# ST_LINK-Wiki.net
KiCad netlist of a schematic drawn in Altium Designer
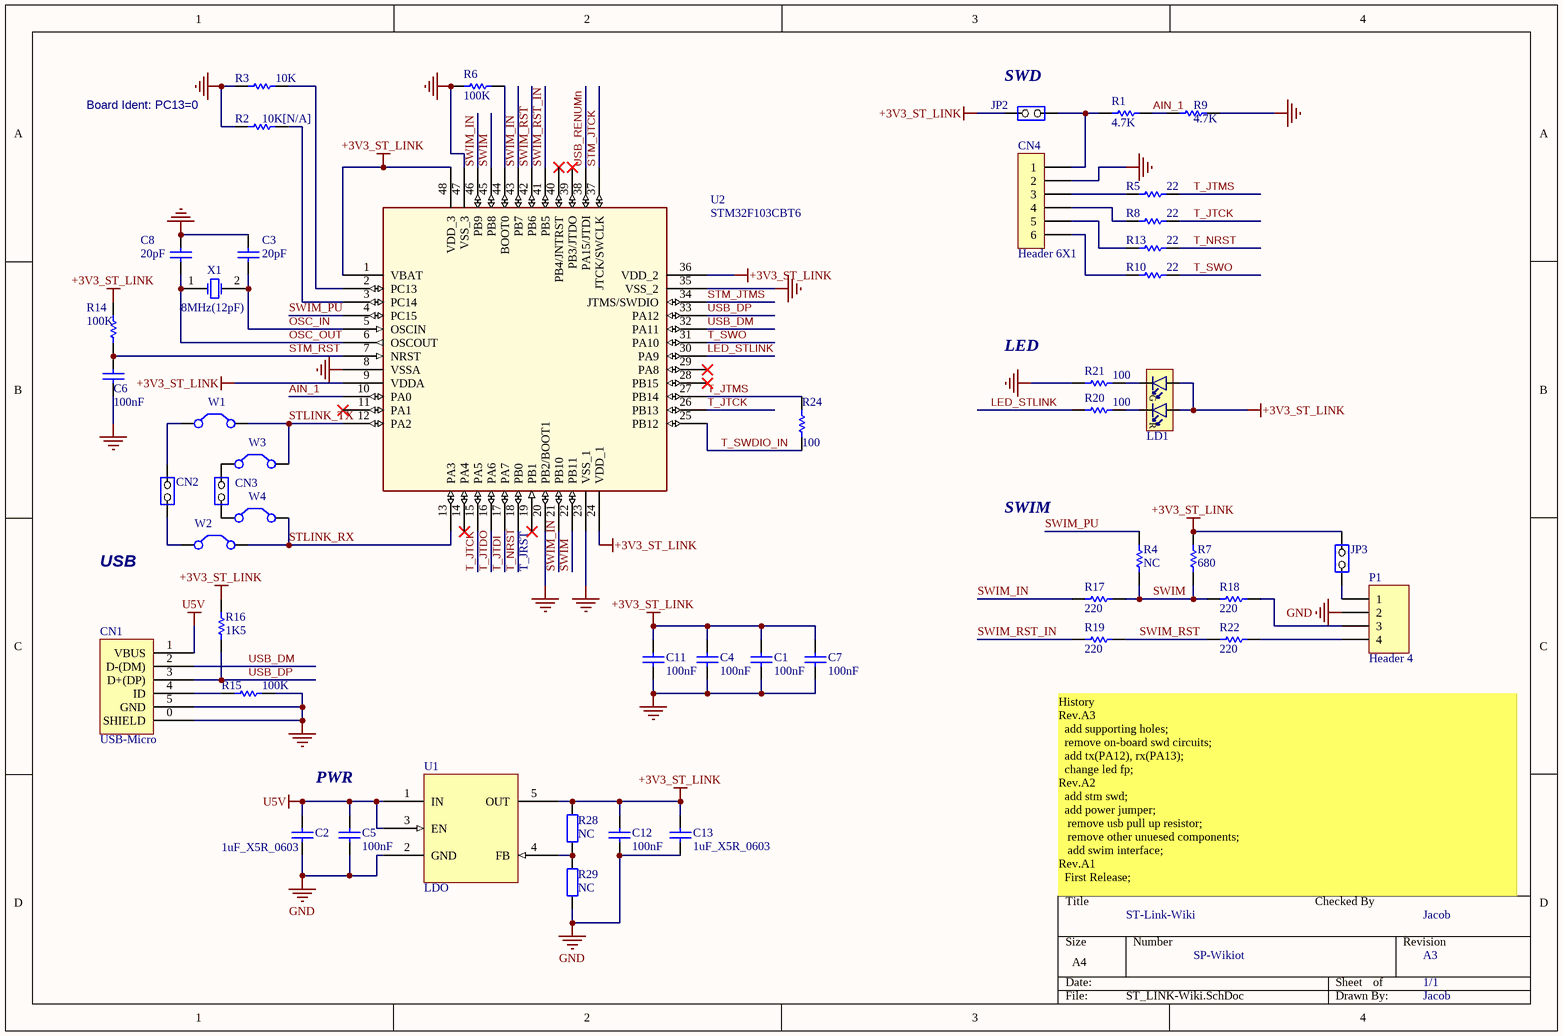
[diagram p0: ST_LINK-Wiki.SchDoc]

(export (version "E")
  (design (tool "Eeschema 10.0.6"))
  (components
    (comp (ref "C1")
      (value "100nF")
      (footprint "0603C")
      (description "Capacitor 0402 / 0603 / 0805")
      (libsource (lib "MCD_TOOLS") (part "Capacitor_ST"))
    )
    (comp (ref "C2")
      (value "1uF_X5R_0603")
      (footprint "0603C")
      (description "0603  X5R 1礔")
      (fields (field (name "TOLERANCE") "10%"))
      (libsource (lib "MB963_1") (part "CAP SMD 0603  X5R 1礔 25V 10%"))
    )
    (comp (ref "C3")
      (value "20pF")
      (footprint "0603C")
      (description "Capacitor 0402 / 0603 / 0805")
      (libsource (lib "MCD_TOOLS") (part "Capacitor_ST"))
    )
    (comp (ref "C4")
      (value "100nF")
      (footprint "0603C")
      (description "Capacitor 0402 / 0603 / 0805")
      (libsource (lib "MCD_TOOLS") (part "Capacitor_ST"))
    )
    (comp (ref "C5")
      (value "100nF")
      (footprint "0603C")
      (description "Capacitor 0402 / 0603 / 0805")
      (libsource (lib "MCD_TOOLS") (part "Capacitor_ST"))
    )
    (comp (ref "C6")
      (value "100nF")
      (footprint "0603C")
      (description "Capacitor 0402 / 0603 / 0805")
      (libsource (lib "MCD_TOOLS") (part "Capacitor_ST"))
    )
    (comp (ref "C7")
      (value "100nF")
      (footprint "0603C")
      (description "Capacitor 0402 / 0603 / 0805")
      (libsource (lib "MCD_TOOLS") (part "Capacitor_ST"))
    )
    (comp (ref "C8")
      (value "20pF")
      (footprint "0603C")
      (description "Capacitor 0402 / 0603 / 0805")
      (libsource (lib "MCD_TOOLS") (part "Capacitor_ST"))
    )
    (comp (ref "C11")
      (value "100nF")
      (footprint "0603C")
      (description "Capacitor 0402 / 0603 / 0805")
      (libsource (lib "MCD_TOOLS") (part "Capacitor_ST"))
    )
    (comp (ref "C12")
      (value "100nF")
      (footprint "0603C")
      (description "Capacitor 0402 / 0603 / 0805")
      (libsource (lib "MCD_TOOLS") (part "Capacitor_ST"))
    )
    (comp (ref "C13")
      (value "1uF_X5R_0603")
      (footprint "0603C")
      (description "0603  X5R 1礔")
      (fields (field (name "TOLERANCE") "10%"))
      (libsource (lib "MB963_1") (part "CAP SMD 0603  X5R 1礔 25V 10%"))
    )
    (comp (ref "CN1")
      (value "USB-Micro")
      (footprint "USB-MICRO-Lite")
      (libsource (lib "Connector") (part "USB-Micro"))
    )
    (comp (ref "CN2") (value "~") (footprint "HDR1X2-L/2.54MM") (libsource (lib "MCD_TOOLS") (part "JP2")))
    (comp (ref "CN3") (value "~") (footprint "HDR1X2-L/2.54MM") (libsource (lib "MCD_TOOLS") (part "JP2")))
    (comp (ref "CN4")
      (value "Header 6X1")
      (footprint "HDR1X6-L/2.54MM")
      (description "Header, 6-Pin, Single row")
      (fields (field (name "PUBLISHER") "Altium Limited"))
      (libsource (lib "Nucleo_64") (part "Header 6X1"))
    )
    (comp (ref "JP2") (value "~") (footprint "HDR1X2/2.54mm") (libsource (lib "*") (part "JP2")))
    (comp (ref "JP3") (value "~") (footprint "HDR1X2/2.54mm") (libsource (lib "*") (part "JP2")))
    (comp (ref "LD1")
      (value "LTST-C195KGJRKT")
      (footprint "0805-LED-Bi")
      (description "Avago, HSMF-A203 Bi-Color LED")
      (fields
        (field (name "MANUFACTURER") "Lite-On Inc")
        (field (name "2ND SOURCE PART NUMBER") "859-LTST-C195KGJRKT")
        (field (name "PUBLISHER") "Nordic Semiconductor")
      )
      (libsource (lib "Misc") (part "LED-DUAL"))
    )
    (comp (ref "P1")
      (value "Header 4")
      (footprint "HDR1X4-L/2.54MM")
      (description "Header, 4-Pin")
      (fields (field (name "PUBLISHER") "Altium Limited"))
      (libsource (lib "Miscellaneous Connectors") (part "Header 4"))
    )
    (comp (ref "R1")
      (value "4.7K")
      (footprint "0603R")
      (description "Resistor 0402 / 0603 / 0805")
      (libsource (lib "Miscellaneous Devices") (part "Res1"))
    )
    (comp (ref "R2")
      (value "10K[N/A]")
      (footprint "0603R")
      (description "Resistor 0402 / 0603 / 0805")
      (libsource (lib "Miscellaneous Devices") (part "Res1"))
    )
    (comp (ref "R3")
      (value "10K")
      (footprint "0603R")
      (description "Resistor 0402 / 0603 / 0805")
      (libsource (lib "Miscellaneous Devices") (part "Res1"))
    )
    (comp (ref "R4")
      (value "NC")
      (footprint "0603R")
      (description "Resistor 0402 / 0603 / 0805")
      (libsource (lib "Miscellaneous Devices") (part "Res1"))
    )
    (comp (ref "R5")
      (value "22")
      (footprint "0603R")
      (description "Resistor 0402 / 0603 / 0805")
      (libsource (lib "Miscellaneous Devices") (part "Res1"))
    )
    (comp (ref "R6")
      (value "100K")
      (footprint "0603R")
      (description "Resistor 0402 / 0603 / 0805")
      (libsource (lib "Miscellaneous Devices") (part "Res1"))
    )
    (comp (ref "R7")
      (value "680")
      (footprint "0603R")
      (description "Resistor 0402 / 0603 / 0805")
      (libsource (lib "Miscellaneous Devices") (part "Res1"))
    )
    (comp (ref "R8")
      (value "22")
      (footprint "0603R")
      (description "Resistor 0402 / 0603 / 0805")
      (libsource (lib "Miscellaneous Devices") (part "Res1"))
    )
    (comp (ref "R9")
      (value "4.7K")
      (footprint "0603R")
      (description "Resistor 0402 / 0603 / 0805")
      (libsource (lib "Miscellaneous Devices") (part "Res1"))
    )
    (comp (ref "R10")
      (value "22")
      (footprint "0603R")
      (description "Resistor 0402 / 0603 / 0805")
      (libsource (lib "Miscellaneous Devices") (part "Res1"))
    )
    (comp (ref "R13")
      (value "22")
      (footprint "0603R")
      (description "Resistor 0402 / 0603 / 0805")
      (libsource (lib "Miscellaneous Devices") (part "Res1"))
    )
    (comp (ref "R14")
      (value "100K")
      (footprint "0603R")
      (description "Resistor 0402 / 0603 / 0805")
      (libsource (lib "Miscellaneous Devices") (part "Res1"))
    )
    (comp (ref "R15")
      (value "100K")
      (footprint "0603R")
      (description "Resistor 0402 / 0603 / 0805")
      (libsource (lib "Miscellaneous Devices") (part "Res1"))
    )
    (comp (ref "R16")
      (value "1K5")
      (footprint "0603R")
      (description "Resistor 0402 / 0603 / 0805")
      (libsource (lib "Miscellaneous Devices") (part "Res1"))
    )
    (comp (ref "R17")
      (value "220")
      (footprint "0603R")
      (description "Resistor 0402 / 0603 / 0805")
      (libsource (lib "Miscellaneous Devices") (part "Res1"))
    )
    (comp (ref "R18")
      (value "220")
      (footprint "0603R")
      (description "Resistor 0402 / 0603 / 0805")
      (libsource (lib "Miscellaneous Devices") (part "Res1"))
    )
    (comp (ref "R19")
      (value "220")
      (footprint "0603R")
      (description "Resistor 0402 / 0603 / 0805")
      (libsource (lib "Miscellaneous Devices") (part "Res1"))
    )
    (comp (ref "R20")
      (value "100")
      (footprint "0603R")
      (description "Resistor 0402 / 0603 / 0805")
      (libsource (lib "Miscellaneous Devices") (part "Res1"))
    )
    (comp (ref "R21")
      (value "100")
      (footprint "0603R")
      (description "Resistor 0402 / 0603 / 0805")
      (libsource (lib "Miscellaneous Devices") (part "Res1"))
    )
    (comp (ref "R22")
      (value "220")
      (footprint "0603R")
      (description "Resistor 0402 / 0603 / 0805")
      (libsource (lib "Miscellaneous Devices") (part "Res1"))
    )
    (comp (ref "R24")
      (value "100")
      (footprint "0603R")
      (description "Resistor 0402 / 0603 / 0805")
      (libsource (lib "Miscellaneous Devices") (part "Res1"))
    )
    (comp (ref "R28")
      (value "NC")
      (footprint "0603M")
      (description "Resistor")
      (fields (field (name "PUBLISHER") "Altium Limited"))
      (libsource (lib "") (part "Res2_1"))
    )
    (comp (ref "R29")
      (value "NC")
      (footprint "0603M")
      (description "Resistor")
      (fields (field (name "PUBLISHER") "Altium Limited"))
      (libsource (lib "Miscellaneous Devices") (part "Res2"))
    )
    (comp (ref "U1")
      (value "LDO")
      (footprint "SOT23-5")
      (description "General LDO SOT23-5")
      (libsource (lib "Power") (part "LDO-SOT23-5"))
    )
    (comp (ref "U2")
      (value "STM32F103CBT6")
      (footprint "QFP48 7X7")
      (description "Medium-density performance line ARM-based 32-bit MCU with 64KB Flash")
      (libsource (lib "Nucleo_64") (part "STM32F103CBT6"))
    )
    (comp (ref "W1")
      (value "Jumper2-1")
      (footprint "JP2_SMD")
      (description "Jumper Wire")
      (fields (field (name "PUBLISHER") "Altium Limited"))
      (libsource (lib "Misc") (part "Jumper2-1"))
    )
    (comp (ref "W2")
      (value "Jumper2-1")
      (footprint "JP2_SMD")
      (description "Jumper Wire")
      (fields (field (name "PUBLISHER") "Altium Limited"))
      (libsource (lib "Misc") (part "Jumper2-1"))
    )
    (comp (ref "W3")
      (value "Jumper2-1")
      (footprint "JP2_SMD")
      (description "Jumper Wire")
      (fields (field (name "PUBLISHER") "Altium Limited"))
      (libsource (lib "Misc") (part "Jumper2-1"))
    )
    (comp (ref "W4")
      (value "Jumper2-1")
      (footprint "JP2_SMD")
      (description "Jumper Wire")
      (fields (field (name "PUBLISHER") "Altium Limited"))
      (libsource (lib "Misc") (part "Jumper2-1"))
    )
    (comp (ref "X1")
      (value "8MHz(12pF)")
      (footprint "XTAL1")
      (description "Crystal Oscillator")
      (fields (field (name "PUBLISHER") "Altium Limited"))
      (libsource (lib "MB963_1") (part "XTAL"))
    )
  )
  (nets
    (net (code "1") (name "+3V3_ST_LINK") (class "Default")
      (node (ref "C1") (pin "2") (pinfunction "2_2") (pintype "passive"))
      (node (ref "C11") (pin "2") (pinfunction "2_2") (pintype "passive"))
      (node (ref "C12") (pin "2") (pinfunction "2_2") (pintype "passive"))
      (node (ref "C13") (pin "1") (pinfunction "1_1") (pintype "passive"))
      (node (ref "C4") (pin "2") (pinfunction "2_2") (pintype "passive"))
      (node (ref "C7") (pin "2") (pinfunction "2_2") (pintype "passive"))
      (node (ref "JP2") (pin "1") (pinfunction "COMMON_1") (pintype "passive"))
      (node (ref "JP3") (pin "1") (pinfunction "COMMON_1") (pintype "passive"))
      (node (ref "LD1") (pin "3") (pinfunction "A2_3") (pintype "passive"))
      (node (ref "LD1") (pin "4") (pinfunction "A1_4") (pintype "passive"))
      (node (ref "R14") (pin "2") (pinfunction "2_2") (pintype "passive"))
      (node (ref "R16") (pin "2") (pinfunction "2_2") (pintype "passive"))
      (node (ref "R28") (pin "1") (pinfunction "1_1") (pintype "passive"))
      (node (ref "R7") (pin "2") (pinfunction "2_2") (pintype "passive"))
      (node (ref "U1") (pin "5") (pinfunction "OUT_5") (pintype "power_in"))
      (node (ref "U2") (pin "1") (pinfunction "VBAT_1") (pintype "power_in"))
      (node (ref "U2") (pin "24") (pinfunction "VDD_1_24") (pintype "power_in"))
      (node (ref "U2") (pin "36") (pinfunction "VDD_2_36") (pintype "power_in"))
      (node (ref "U2") (pin "48") (pinfunction "VDD_3_48") (pintype "power_in"))
      (node (ref "U2") (pin "9") (pinfunction "VDDA_9") (pintype "power_in"))
    )
    (net (code "2") (name "/AIN_1") (class "Default")
      (node (ref "R1") (pin "1") (pinfunction "1_1") (pintype "passive"))
      (node (ref "R9") (pin "1") (pinfunction "1_1") (pintype "passive"))
      (node (ref "U2") (pin "10") (pinfunction "PA0_10") (pintype "bidirectional"))
    )
    (net (code "3") (name "/LED_STLINK") (class "Default")
      (node (ref "R20") (pin "1") (pinfunction "1_1") (pintype "passive"))
      (node (ref "U2") (pin "30") (pinfunction "PA9_30") (pintype "bidirectional"))
    )
    (net (code "4") (name "/OSC_IN") (class "Default")
      (node (ref "C3") (pin "1") (pinfunction "1_1") (pintype "passive"))
      (node (ref "U2") (pin "5") (pinfunction "OSCIN_5") (pintype "input"))
      (node (ref "X1") (pin "2") (pinfunction "OSC2_2") (pintype "passive"))
    )
    (net (code "5") (name "/OSC_OUT") (class "Default")
      (node (ref "C8") (pin "1") (pinfunction "1_1") (pintype "passive"))
      (node (ref "U2") (pin "6") (pinfunction "OSCOUT_6") (pintype "output"))
      (node (ref "X1") (pin "1") (pinfunction "OSC1_1") (pintype "passive"))
    )
    (net (code "6") (name "/STLINK_RX") (class "Default")
      (node (ref "U2") (pin "13") (pinfunction "PA3_13") (pintype "bidirectional"))
      (node (ref "W2") (pin "2") (pinfunction "C2_2") (pintype "passive"))
      (node (ref "W4") (pin "2") (pinfunction "C2_2") (pintype "passive"))
    )
    (net (code "7") (name "/STLINK_TX") (class "Default")
      (node (ref "U2") (pin "12") (pinfunction "PA2_12") (pintype "bidirectional"))
      (node (ref "W1") (pin "2") (pinfunction "C2_2") (pintype "passive"))
      (node (ref "W3") (pin "2") (pinfunction "C2_2") (pintype "passive"))
    )
    (net (code "8") (name "/STM_JTCK") (class "Default")
      (node (ref "U2") (pin "37") (pinfunction "JTCK/SWCLK_37") (pintype "bidirectional"))
    )
    (net (code "9") (name "/STM_JTMS") (class "Default")
      (node (ref "U2") (pin "34") (pinfunction "JTMS/SWDIO_34") (pintype "bidirectional"))
    )
    (net (code "10") (name "/STM_RST") (class "Default")
      (node (ref "C6") (pin "2") (pinfunction "2_2") (pintype "passive"))
      (node (ref "R14") (pin "1") (pinfunction "1_1") (pintype "passive"))
      (node (ref "U2") (pin "7") (pinfunction "NRST_7") (pintype "input"))
    )
    (net (code "11") (name "/SWIM") (class "Default")
      (node (ref "R17") (pin "2") (pinfunction "2_2") (pintype "passive"))
      (node (ref "R18") (pin "1") (pinfunction "1_1") (pintype "passive"))
      (node (ref "R4") (pin "1") (pinfunction "1_1") (pintype "passive"))
      (node (ref "R7") (pin "1") (pinfunction "1_1") (pintype "passive"))
      (node (ref "U2") (pin "22") (pinfunction "PB11_22") (pintype "bidirectional"))
      (node (ref "U2") (pin "45") (pinfunction "PB8_45") (pintype "bidirectional"))
    )
    (net (code "12") (name "/SWIM_IN") (class "Default")
      (node (ref "R17") (pin "1") (pinfunction "1_1") (pintype "passive"))
      (node (ref "U2") (pin "21") (pinfunction "PB10_21") (pintype "bidirectional"))
      (node (ref "U2") (pin "43") (pinfunction "PB7_43") (pintype "bidirectional"))
      (node (ref "U2") (pin "46") (pinfunction "PB9_46") (pintype "bidirectional"))
    )
    (net (code "13") (name "/SWIM_PU") (class "Default")
      (node (ref "R4") (pin "2") (pinfunction "2_2") (pintype "passive"))
      (node (ref "U2") (pin "4") (pinfunction "PC15_4") (pintype "bidirectional"))
    )
    (net (code "14") (name "/SWIM_RST") (class "Default")
      (node (ref "R19") (pin "2") (pinfunction "2_2") (pintype "passive"))
      (node (ref "R22") (pin "1") (pinfunction "1_1") (pintype "passive"))
      (node (ref "U2") (pin "42") (pinfunction "PB6_42") (pintype "bidirectional"))
    )
    (net (code "15") (name "/SWIM_RST_IN") (class "Default")
      (node (ref "R19") (pin "1") (pinfunction "1_1") (pintype "passive"))
      (node (ref "U2") (pin "41") (pinfunction "PB5_41") (pintype "bidirectional"))
    )
    (net (code "16") (name "/T_JTCK") (class "Default")
      (node (ref "R8") (pin "2") (pinfunction "2_2") (pintype "passive"))
      (node (ref "U2") (pin "15") (pinfunction "PA5_15") (pintype "bidirectional"))
      (node (ref "U2") (pin "26") (pinfunction "PB13_26") (pintype "bidirectional"))
    )
    (net (code "17") (name "/T_JTDI") (class "Default")
      (node (ref "U2") (pin "17") (pinfunction "PA7_17") (pintype "bidirectional"))
    )
    (net (code "18") (name "/T_JTDO") (class "Default")
      (node (ref "U2") (pin "16") (pinfunction "PA6_16") (pintype "bidirectional"))
    )
    (net (code "19") (name "/T_JTMS") (class "Default")
      (node (ref "R24") (pin "2") (pinfunction "2_2") (pintype "passive"))
      (node (ref "R5") (pin "2") (pinfunction "2_2") (pintype "passive"))
      (node (ref "U2") (pin "27") (pinfunction "PB14_27") (pintype "bidirectional"))
    )
    (net (code "20") (name "/T_NRST") (class "Default")
      (node (ref "R13") (pin "2") (pinfunction "2_2") (pintype "passive"))
      (node (ref "U2") (pin "18") (pinfunction "PB0_18") (pintype "bidirectional"))
    )
    (net (code "21") (name "/T_SWDIO_IN") (class "Default")
      (node (ref "R24") (pin "1") (pinfunction "1_1") (pintype "passive"))
      (node (ref "U2") (pin "25") (pinfunction "PB12_25") (pintype "bidirectional"))
    )
    (net (code "22") (name "/T_SWO") (class "Default")
      (node (ref "R10") (pin "2") (pinfunction "2_2") (pintype "passive"))
      (node (ref "U2") (pin "31") (pinfunction "PA10_31") (pintype "bidirectional"))
    )
    (net (code "23") (name "/USB_DM") (class "Default")
      (node (ref "CN1") (pin "2") (pinfunction "D-(DM)_2") (pintype "passive"))
      (node (ref "U2") (pin "32") (pinfunction "PA11_32") (pintype "bidirectional"))
    )
    (net (code "24") (name "/USB_DP") (class "Default")
      (node (ref "CN1") (pin "3") (pinfunction "D+(DP)_3") (pintype "passive"))
      (node (ref "R16") (pin "1") (pinfunction "1_1") (pintype "passive"))
      (node (ref "U2") (pin "33") (pinfunction "PA12_33") (pintype "bidirectional"))
    )
    (net (code "25") (name "/USB_RENUMn") (class "Default")
      (node (ref "U2") (pin "38") (pinfunction "PA15/JTDI_38") (pintype "bidirectional"))
    )
    (net (code "26") (name "GND") (class "Default")
      (node (ref "C1") (pin "1") (pinfunction "1_1") (pintype "passive"))
      (node (ref "C11") (pin "1") (pinfunction "1_1") (pintype "passive"))
      (node (ref "C12") (pin "1") (pinfunction "1_1") (pintype "passive"))
      (node (ref "C13") (pin "2") (pinfunction "2_2") (pintype "passive"))
      (node (ref "C2") (pin "1") (pinfunction "1_1") (pintype "passive"))
      (node (ref "C3") (pin "2") (pinfunction "2_2") (pintype "passive"))
      (node (ref "C4") (pin "1") (pinfunction "1_1") (pintype "passive"))
      (node (ref "C5") (pin "1") (pinfunction "1_1") (pintype "passive"))
      (node (ref "C6") (pin "1") (pinfunction "1_1") (pintype "passive"))
      (node (ref "C7") (pin "1") (pinfunction "1_1") (pintype "passive"))
      (node (ref "C8") (pin "2") (pinfunction "2_2") (pintype "passive"))
      (node (ref "CN1") (pin "0") (pinfunction "SHIELD_0") (pintype "passive"))
      (node (ref "CN1") (pin "5") (pinfunction "GND_5") (pintype "passive"))
      (node (ref "CN4") (pin "2") (pinfunction "2_2") (pintype "passive"))
      (node (ref "P1") (pin "2") (pinfunction "2_2") (pintype "passive"))
      (node (ref "R15") (pin "2") (pinfunction "2_2") (pintype "passive"))
      (node (ref "R2") (pin "1") (pinfunction "1_1") (pintype "passive"))
      (node (ref "R21") (pin "1") (pinfunction "1_1") (pintype "passive"))
      (node (ref "R29") (pin "1") (pinfunction "1_1") (pintype "passive"))
      (node (ref "R3") (pin "1") (pinfunction "1_1") (pintype "passive"))
      (node (ref "R6") (pin "1") (pinfunction "1_1") (pintype "passive"))
      (node (ref "R9") (pin "2") (pinfunction "2_2") (pintype "passive"))
      (node (ref "U1") (pin "2") (pinfunction "GND_2") (pintype "power_in"))
      (node (ref "U2") (pin "20") (pinfunction "PB2/BOOT1_20") (pintype "bidirectional"))
      (node (ref "U2") (pin "23") (pinfunction "VSS_1_23") (pintype "power_in"))
      (node (ref "U2") (pin "35") (pinfunction "VSS_2_35") (pintype "power_in"))
      (node (ref "U2") (pin "47") (pinfunction "VSS_3_47") (pintype "power_in"))
      (node (ref "U2") (pin "8") (pinfunction "VSSA_8") (pintype "power_in"))
    )
    (net (code "27") (name "Net-(CN1-ID)") (class "Default")
      (node (ref "CN1") (pin "4") (pinfunction "ID_4") (pintype "passive"))
      (node (ref "R15") (pin "1") (pinfunction "1_1") (pintype "passive"))
    )
    (net (code "28") (name "Net-(CN2-COMMON)") (class "Default")
      (node (ref "CN2") (pin "1") (pinfunction "COMMON_1") (pintype "passive"))
      (node (ref "W2") (pin "1") (pinfunction "C1_1") (pintype "passive"))
    )
    (net (code "29") (name "Net-(CN2-NO)") (class "Default")
      (node (ref "CN2") (pin "2") (pinfunction "NO_2") (pintype "passive"))
      (node (ref "W1") (pin "1") (pinfunction "C1_1") (pintype "passive"))
    )
    (net (code "30") (name "Net-(CN3-COMMON)") (class "Default")
      (node (ref "CN3") (pin "1") (pinfunction "COMMON_1") (pintype "passive"))
      (node (ref "W4") (pin "1") (pinfunction "C1_1") (pintype "passive"))
    )
    (net (code "31") (name "Net-(CN3-NO)") (class "Default")
      (node (ref "CN3") (pin "2") (pinfunction "NO_2") (pintype "passive"))
      (node (ref "W3") (pin "1") (pinfunction "C1_1") (pintype "passive"))
    )
    (net (code "32") (name "Net-(CN4-Pad3)") (class "Default")
      (node (ref "CN4") (pin "3") (pinfunction "3_3") (pintype "passive"))
      (node (ref "R5") (pin "1") (pinfunction "1_1") (pintype "passive"))
    )
    (net (code "33") (name "Net-(CN4-Pad4)") (class "Default")
      (node (ref "CN4") (pin "4") (pinfunction "4_4") (pintype "passive"))
      (node (ref "R8") (pin "1") (pinfunction "1_1") (pintype "passive"))
    )
    (net (code "34") (name "Net-(CN4-Pad5)") (class "Default")
      (node (ref "CN4") (pin "5") (pinfunction "5_5") (pintype "passive"))
      (node (ref "R13") (pin "1") (pinfunction "1_1") (pintype "passive"))
    )
    (net (code "35") (name "Net-(CN4-Pad6)") (class "Default")
      (node (ref "CN4") (pin "6") (pinfunction "6_6") (pintype "passive"))
      (node (ref "R10") (pin "1") (pinfunction "1_1") (pintype "passive"))
    )
    (net (code "36") (name "Net-(JP2-NO)") (class "Default")
      (node (ref "CN4") (pin "1") (pinfunction "1_1") (pintype "passive"))
      (node (ref "JP2") (pin "2") (pinfunction "NO_2") (pintype "passive"))
      (node (ref "R1") (pin "2") (pinfunction "2_2") (pintype "passive"))
    )
    (net (code "37") (name "Net-(JP3-NO)") (class "Default")
      (node (ref "JP3") (pin "2") (pinfunction "NO_2") (pintype "passive"))
      (node (ref "P1") (pin "1") (pinfunction "1_1") (pintype "passive"))
    )
    (net (code "38") (name "Net-(LD1-C1)") (class "Default")
      (node (ref "LD1") (pin "1") (pinfunction "C1_1") (pintype "passive"))
      (node (ref "R21") (pin "2") (pinfunction "2_2") (pintype "passive"))
    )
    (net (code "39") (name "Net-(LD1-C2)") (class "Default")
      (node (ref "LD1") (pin "2") (pinfunction "C2_2") (pintype "passive"))
      (node (ref "R20") (pin "2") (pinfunction "2_2") (pintype "passive"))
    )
    (net (code "40") (name "Net-(P1-Pad3)") (class "Default")
      (node (ref "P1") (pin "3") (pinfunction "3_3") (pintype "passive"))
      (node (ref "R18") (pin "2") (pinfunction "2_2") (pintype "passive"))
    )
    (net (code "41") (name "Net-(P1-Pad4)") (class "Default")
      (node (ref "P1") (pin "4") (pinfunction "4_4") (pintype "passive"))
      (node (ref "R22") (pin "2") (pinfunction "2_2") (pintype "passive"))
    )
    (net (code "42") (name "Net-(U1-FB)") (class "Default")
      (node (ref "R28") (pin "2") (pinfunction "2_2") (pintype "passive"))
      (node (ref "R29") (pin "2") (pinfunction "2_2") (pintype "passive"))
      (node (ref "U1") (pin "4") (pinfunction "FB_4") (pintype "input"))
    )
    (net (code "43") (name "Net-(U2-BOOT0)") (class "Default")
      (node (ref "R6") (pin "2") (pinfunction "2_2") (pintype "passive"))
      (node (ref "U2") (pin "44") (pinfunction "BOOT0_44") (pintype "bidirectional"))
    )
    (net (code "44") (name "Net-(U2-PC13)") (class "Default")
      (node (ref "R3") (pin "2") (pinfunction "2_2") (pintype "passive"))
      (node (ref "U2") (pin "2") (pinfunction "PC13_2") (pintype "bidirectional"))
    )
    (net (code "45") (name "Net-(U2-PC14)") (class "Default")
      (node (ref "R2") (pin "2") (pinfunction "2_2") (pintype "passive"))
      (node (ref "U2") (pin "3") (pinfunction "PC14_3") (pintype "bidirectional"))
    )
    (net (code "46") (name "U5V") (class "Default")
      (node (ref "C2") (pin "2") (pinfunction "2_2") (pintype "passive"))
      (node (ref "C5") (pin "2") (pinfunction "2_2") (pintype "passive"))
      (node (ref "CN1") (pin "1") (pinfunction "VBUS_1") (pintype "passive"))
      (node (ref "U1") (pin "1") (pinfunction "IN_1") (pintype "power_in"))
      (node (ref "U1") (pin "3") (pinfunction "EN_3") (pintype "input"))
    )
    (net (code "47") (name "unconnected-(U2-PA1-Pad11)") (class "Default")
      (node (ref "U2") (pin "11") (pinfunction "PA1_11") (pintype "bidirectional+no_connect"))
    )
    (net (code "48") (name "unconnected-(U2-PA4-Pad14)") (class "Default")
      (node (ref "U2") (pin "14") (pinfunction "PA4_14") (pintype "bidirectional+no_connect"))
    )
    (net (code "49") (name "unconnected-(U2-PA8-Pad29)") (class "Default")
      (node (ref "U2") (pin "29") (pinfunction "PA8_29") (pintype "bidirectional+no_connect"))
    )
    (net (code "50") (name "unconnected-(U2-PB1-Pad19)") (class "Default")
      (node (ref "U2") (pin "19") (pinfunction "PB1_19") (pintype "input+no_connect"))
    )
    (net (code "51") (name "unconnected-(U2-PB3{slash}JTDO-Pad39)") (class "Default")
      (node (ref "U2") (pin "39") (pinfunction "PB3/JTDO_39") (pintype "bidirectional+no_connect"))
    )
    (net (code "52") (name "unconnected-(U2-PB4{slash}JNTRST-Pad40)") (class "Default")
      (node (ref "U2") (pin "40") (pinfunction "PB4/JNTRST_40") (pintype "bidirectional+no_connect"))
    )
    (net (code "53") (name "unconnected-(U2-PB15-Pad28)") (class "Default")
      (node (ref "U2") (pin "28") (pinfunction "PB15_28") (pintype "bidirectional+no_connect"))
    )
  )
)
